# Sensors_ADC.net
KiCad netlist of a schematic drawn in Altium Designer
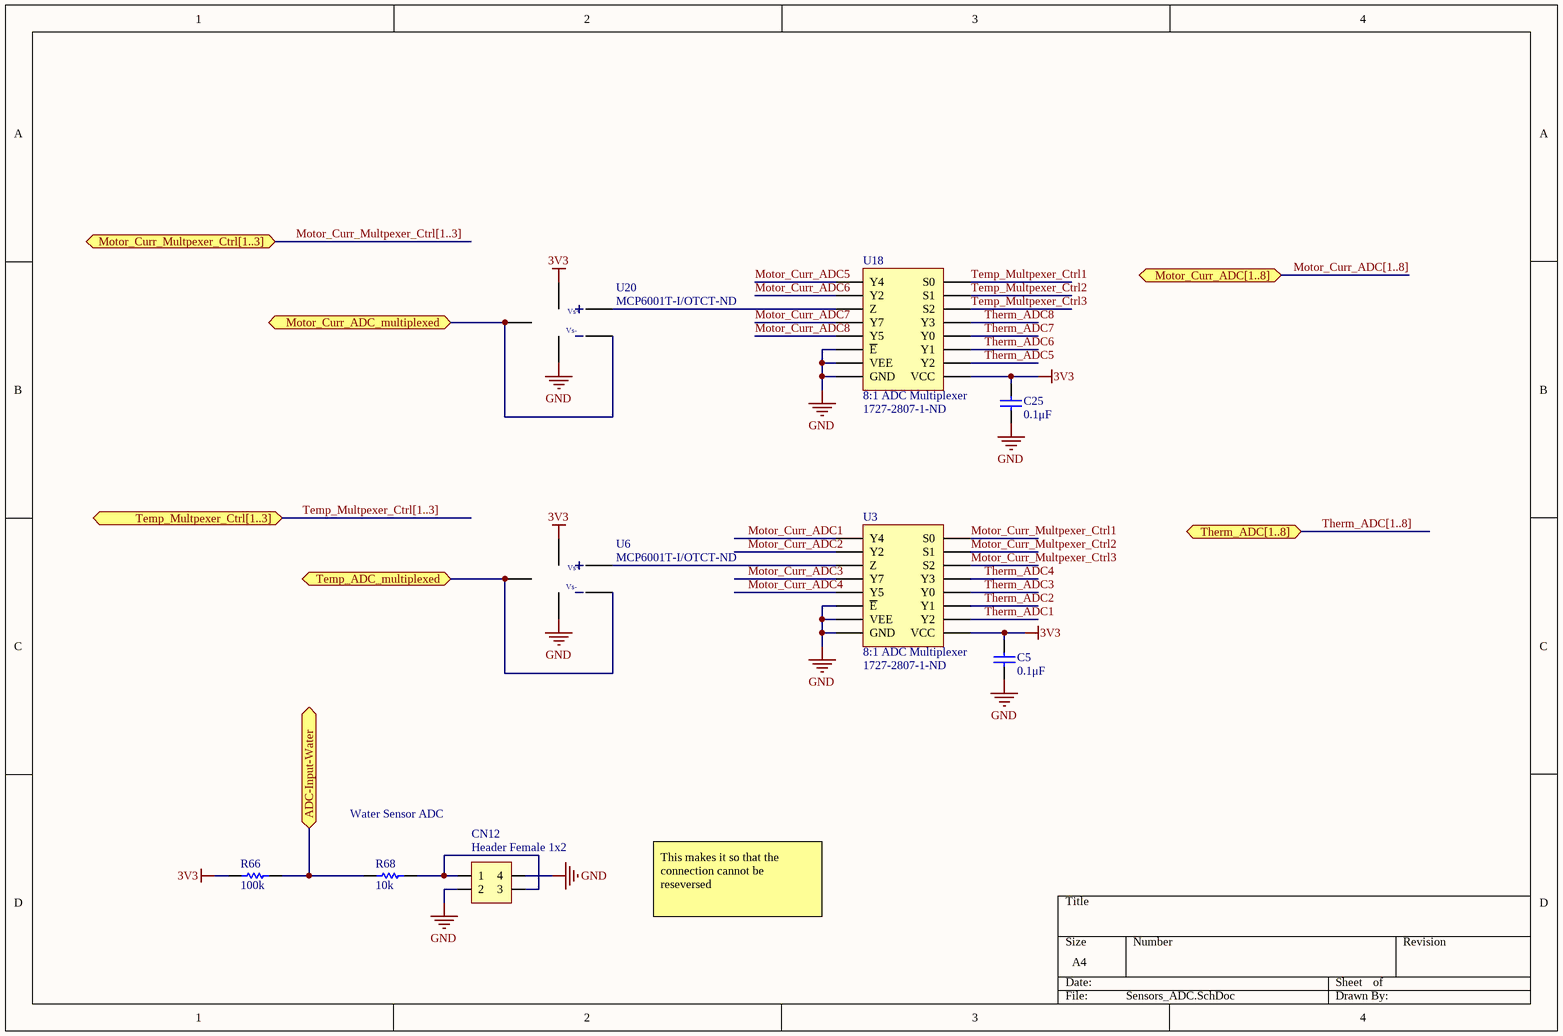
[diagram p0: Sensors_ADC.SchDoc]

(export (version "E")
  (design (tool "Eeschema 10.0.6"))
  (components
    (comp (ref "C5")
      (value "0.1μF")
      (footprint "CAPC1608N(0603\")")
      (description "Capacitor, Ceramic, 100V, +/- 10%, 0603 SMD, X7R")
      (fields
        (field (name "MFG") "TDK")
        (field (name "PUBLISHER") "AUVic")
        (field (name "CREATED BY") "Ashwin Sira")
      )
      (libsource (lib "AUVic_Integrated_Library_Capacitors") (part "0.1uF 100V 0603 SMD, Ceramic"))
    )
    (comp (ref "C25")
      (value "0.1μF")
      (footprint "CAPC1608N(0603\")")
      (description "Capacitor, Ceramic, 100V, +/- 10%, 0603 SMD, X7R")
      (fields
        (field (name "MFG") "TDK")
        (field (name "PUBLISHER") "AUVic")
        (field (name "CREATED BY") "Ashwin Sira")
      )
      (libsource (lib "AUVic_Integrated_Library_Capacitors") (part "0.1uF 100V 0603 SMD, Ceramic"))
    )
    (comp (ref "CN12")
      (value "Header Female 1x2")
      (footprint "Header, Female, 2x2, THT")
      (description "2x2, Pads Pitch: 0.1\" (2.54mm), Through hole")
      (libsource (lib "AUVic_Integrated_Library_Connectors") (part "Header, Female, 2x2"))
    )
    (comp (ref "R66")
      (value "100k")
      (footprint "RESC1608N(0603\")")
      (description "100kR, 1%, 1/10W, 0603 SMD")
      (fields (field (name "MADE BY") "Andy Bates"))
      (libsource (lib "AUVic_Integrated_Library_Resistors") (part "100kR, 1%, 1/10W, 0603 SMD"))
    )
    (comp (ref "R68")
      (value "10k")
      (footprint "RESC1608N(0603\")")
      (description "10kR, 1%, 1/10W, 0603 SMD")
      (fields (field (name "MADE BY") "Ashwin Sira"))
      (libsource (lib "AUVic_Integrated_Library_Resistors") (part "10kR, 1%, 1/10W, 0603 SMD"))
    )
    (comp (ref "U3")
      (value "8:1 ADC Multiplexer")
      (footprint "SOIC-16")
      (fields (field (name "SUPPLIER PART NUMBER 1") "1727-2807-1-ND") (field (name "MADE BY") "Andy Bates"))
      (libsource (lib "AUVic_Schematic_Library_Sensors") (part "74HC4051D,653"))
    )
    (comp (ref "U6")
      (value "Op amp 1.8-6V rail-to-rail (SOT23-5)")
      (footprint "SOT23-5")
      (fields
        (field (name "SUPPLIER PART NUMBER 1") "MCP6001T-I/OTCT-ND")
        (field (name "MADE BY") "Andy Bates")
      )
      (libsource (lib "AUVic_Schematic_Library_Op_amps") (part "Op amp 1.8-6V rail-to-rail (SOT23-5)"))
    )
    (comp (ref "U18")
      (value "8:1 ADC Multiplexer")
      (footprint "SOIC-16")
      (fields (field (name "SUPPLIER PART NUMBER 1") "1727-2807-1-ND") (field (name "MADE BY") "Andy Bates"))
      (libsource (lib "AUVic_Schematic_Library_Sensors") (part "74HC4051D,653"))
    )
    (comp (ref "U20")
      (value "Op amp 1.8-6V rail-to-rail (SOT23-5)")
      (footprint "SOT23-5")
      (fields
        (field (name "SUPPLIER PART NUMBER 1") "MCP6001T-I/OTCT-ND")
        (field (name "MADE BY") "Andy Bates")
      )
      (libsource (lib "AUVic_Schematic_Library_Op_amps") (part "Op amp 1.8-6V rail-to-rail (SOT23-5)"))
    )
  )
  (nets
    (net (code "1") (name "/ADC-Input-Water") (class "Default")
      (node (ref "R66") (pin "2") (pinfunction "2_2") (pintype "passive"))
      (node (ref "R68") (pin "1") (pinfunction "1_1") (pintype "passive"))
    )
    (net (code "2") (name "/Motor_Curr_ADC1") (class "Default")
      (node (ref "U3") (pin "1") (pinfunction "Y4_1") (pintype "passive"))
    )
    (net (code "3") (name "/Motor_Curr_ADC2") (class "Default")
      (node (ref "U3") (pin "2") (pinfunction "Y2_2") (pintype "passive"))
    )
    (net (code "4") (name "/Motor_Curr_ADC3") (class "Default")
      (node (ref "U3") (pin "4") (pinfunction "Y7_4") (pintype "passive"))
    )
    (net (code "5") (name "/Motor_Curr_ADC4") (class "Default")
      (node (ref "U3") (pin "5") (pinfunction "Y5_5") (pintype "passive"))
    )
    (net (code "6") (name "/Motor_Curr_ADC5") (class "Default")
      (node (ref "U18") (pin "1") (pinfunction "Y4_1") (pintype "passive"))
    )
    (net (code "7") (name "/Motor_Curr_ADC6") (class "Default")
      (node (ref "U18") (pin "2") (pinfunction "Y2_2") (pintype "passive"))
    )
    (net (code "8") (name "/Motor_Curr_ADC7") (class "Default")
      (node (ref "U18") (pin "4") (pinfunction "Y7_4") (pintype "passive"))
    )
    (net (code "9") (name "/Motor_Curr_ADC8") (class "Default")
      (node (ref "U18") (pin "5") (pinfunction "Y5_5") (pintype "passive"))
    )
    (net (code "11") (name "/Motor_Curr_ADC_multiplexed") (class "Default")
      (node (ref "U20") (pin "1") (pinfunction "Out_1") (pintype "passive"))
      (node (ref "U20") (pin "4") (pinfunction "V-_4") (pintype "passive"))
    )
    (net (code "12") (name "/Motor_Curr_Multpexer_Ctrl1") (class "Default")
      (node (ref "U3") (pin "9") (pinfunction "S0_9") (pintype "passive"))
    )
    (net (code "13") (name "/Motor_Curr_Multpexer_Ctrl2") (class "Default")
      (node (ref "U3") (pin "10") (pinfunction "S1_10") (pintype "passive"))
    )
    (net (code "14") (name "/Motor_Curr_Multpexer_Ctrl3") (class "Default")
      (node (ref "U3") (pin "11") (pinfunction "S2_11") (pintype "passive"))
    )
    (net (code "16") (name "/Temp_ADC_multiplexed") (class "Default")
      (node (ref "U6") (pin "1") (pinfunction "Out_1") (pintype "passive"))
      (node (ref "U6") (pin "4") (pinfunction "V-_4") (pintype "passive"))
    )
    (net (code "17") (name "/Temp_Multpexer_Ctrl1") (class "Default")
      (node (ref "U18") (pin "9") (pinfunction "S0_9") (pintype "passive"))
    )
    (net (code "18") (name "/Temp_Multpexer_Ctrl2") (class "Default")
      (node (ref "U18") (pin "10") (pinfunction "S1_10") (pintype "passive"))
    )
    (net (code "19") (name "/Temp_Multpexer_Ctrl3") (class "Default")
      (node (ref "U18") (pin "11") (pinfunction "S2_11") (pintype "passive"))
    )
    (net (code "21") (name "/Therm_ADC1") (class "Default")
      (node (ref "U3") (pin "15") (pinfunction "Y2_15") (pintype "passive"))
    )
    (net (code "22") (name "/Therm_ADC2") (class "Default")
      (node (ref "U3") (pin "14") (pinfunction "Y1_14") (pintype "passive"))
    )
    (net (code "23") (name "/Therm_ADC3") (class "Default")
      (node (ref "U3") (pin "13") (pinfunction "Y0_13") (pintype "passive"))
    )
    (net (code "24") (name "/Therm_ADC4") (class "Default")
      (node (ref "U3") (pin "12") (pinfunction "Y3_12") (pintype "passive"))
    )
    (net (code "25") (name "/Therm_ADC5") (class "Default")
      (node (ref "U18") (pin "15") (pinfunction "Y2_15") (pintype "passive"))
    )
    (net (code "26") (name "/Therm_ADC6") (class "Default")
      (node (ref "U18") (pin "14") (pinfunction "Y1_14") (pintype "passive"))
    )
    (net (code "27") (name "/Therm_ADC7") (class "Default")
      (node (ref "U18") (pin "13") (pinfunction "Y0_13") (pintype "passive"))
    )
    (net (code "28") (name "/Therm_ADC8") (class "Default")
      (node (ref "U18") (pin "12") (pinfunction "Y3_12") (pintype "passive"))
    )
    (net (code "30") (name "3V3") (class "Default")
      (node (ref "C25") (pin "2") (pinfunction "Cathode_2") (pintype "passive"))
      (node (ref "C5") (pin "2") (pinfunction "Cathode_2") (pintype "passive"))
      (node (ref "R66") (pin "1") (pinfunction "1_1") (pintype "passive"))
      (node (ref "U18") (pin "16") (pinfunction "VCC_16") (pintype "passive"))
      (node (ref "U20") (pin "5") (pinfunction "Vcc_+_5") (pintype "passive"))
      (node (ref "U3") (pin "16") (pinfunction "VCC_16") (pintype "passive"))
      (node (ref "U6") (pin "5") (pinfunction "Vcc_+_5") (pintype "passive"))
    )
    (net (code "31") (name "GND") (class "Default")
      (node (ref "C25") (pin "1") (pinfunction "Anode_1") (pintype "passive"))
      (node (ref "C5") (pin "1") (pinfunction "Anode_1") (pintype "passive"))
      (node (ref "CN12") (pin "2") (pinfunction "2_2") (pintype "passive"))
      (node (ref "CN12") (pin "4") (pinfunction "4_4") (pintype "passive"))
      (node (ref "U18") (pin "6") (pinfunction "~{E}_6") (pintype "passive"))
      (node (ref "U18") (pin "7") (pinfunction "VEE_7") (pintype "passive"))
      (node (ref "U18") (pin "8") (pinfunction "GND_8") (pintype "passive"))
      (node (ref "U20") (pin "2") (pinfunction "Vcc-_2") (pintype "passive"))
      (node (ref "U3") (pin "6") (pinfunction "~{E}_6") (pintype "passive"))
      (node (ref "U3") (pin "7") (pinfunction "VEE_7") (pintype "passive"))
      (node (ref "U3") (pin "8") (pinfunction "GND_8") (pintype "passive"))
      (node (ref "U6") (pin "2") (pinfunction "Vcc-_2") (pintype "passive"))
    )
    (net (code "32") (name "Net-(CN12-Pad1)") (class "Default")
      (node (ref "CN12") (pin "1") (pinfunction "1_1") (pintype "passive"))
      (node (ref "CN12") (pin "3") (pinfunction "3_3") (pintype "passive"))
      (node (ref "R68") (pin "2") (pinfunction "2_2") (pintype "passive"))
    )
    (net (code "33") (name "Net-(U3-Z)") (class "Default")
      (node (ref "U3") (pin "3") (pinfunction "Z_3") (pintype "passive"))
      (node (ref "U6") (pin "3") (pinfunction "V+_3") (pintype "passive"))
    )
    (net (code "34") (name "Net-(U18-Z)") (class "Default")
      (node (ref "U18") (pin "3") (pinfunction "Z_3") (pintype "passive"))
      (node (ref "U20") (pin "3") (pinfunction "V+_3") (pintype "passive"))
    )
  )
)
